# Controller.net
KiCad netlist of a schematic drawn in Altium Designer
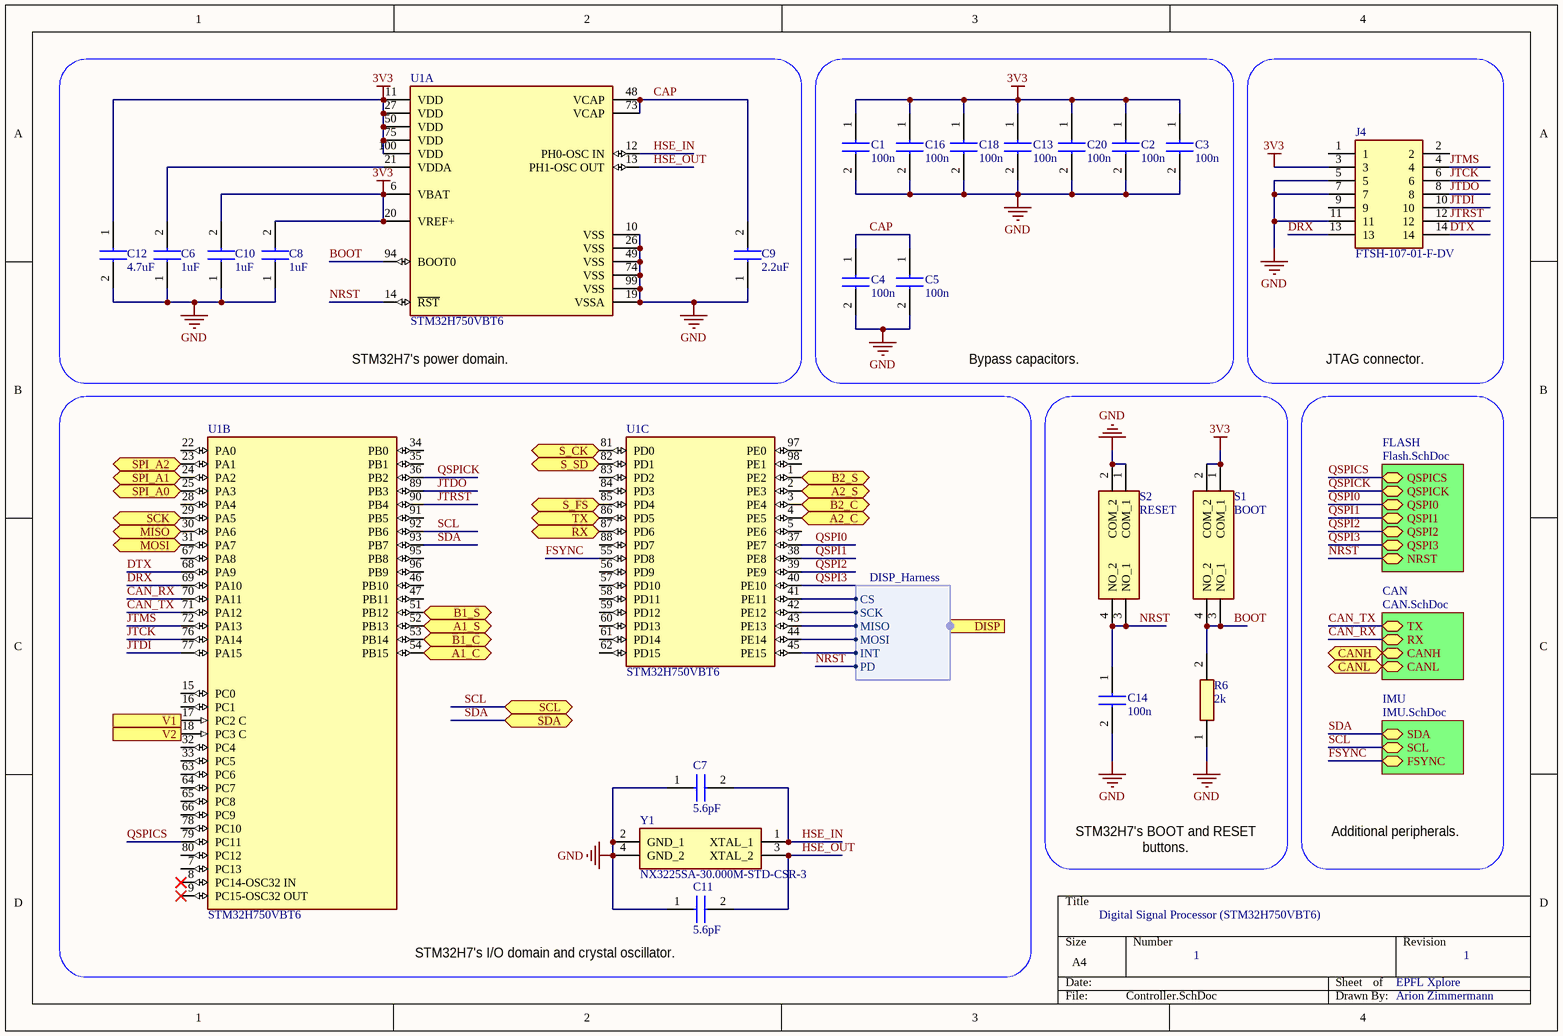
[diagram p0: Controller.SchDoc]

(export (version "E")
  (design (tool "Eeschema 10.0.6"))
  (components
    (comp (ref "C1")
      (value "100n")
      (footprint "SamacSys:CAPC1608X95N")
      (description "Capacitor")
      (fields
        (field (name "MANUFACTURER_PART_NUMBER") "C0603C104K5RACTU")
        (field (name "MOUSER PART NUMBER") "80-C0603C104K5R")
      )
      (libsource (lib "CarrierBoard") (part "C0603C104K5RACTU"))
    )
    (comp (ref "C2")
      (value "100n")
      (footprint "SamacSys:CAPC1608X95N")
      (description "Capacitor")
      (fields
        (field (name "MANUFACTURER_PART_NUMBER") "C0603C104K5RACTU")
        (field (name "MOUSER PART NUMBER") "80-C0603C104K5R")
      )
      (libsource (lib "CarrierBoard") (part "C0603C104K5RACTU"))
    )
    (comp (ref "C3")
      (value "100n")
      (footprint "SamacSys:CAPC1608X95N")
      (description "Capacitor")
      (fields
        (field (name "MANUFACTURER_PART_NUMBER") "C0603C104K5RACTU")
        (field (name "MOUSER PART NUMBER") "80-C0603C104K5R")
      )
      (libsource (lib "CarrierBoard") (part "C0603C104K5RACTU"))
    )
    (comp (ref "C4")
      (value "100n")
      (footprint "SamacSys:CAPC1608X95N")
      (description "Capacitor")
      (fields
        (field (name "MANUFACTURER_PART_NUMBER") "C0603C104K5RACTU")
        (field (name "MOUSER PART NUMBER") "80-C0603C104K5R")
      )
      (libsource (lib "CarrierBoard") (part "C0603C104K5RACTU"))
    )
    (comp (ref "C5")
      (value "100n")
      (footprint "SamacSys:CAPC1608X95N")
      (description "Capacitor")
      (fields
        (field (name "MANUFACTURER_PART_NUMBER") "C0603C104K5RACTU")
        (field (name "MOUSER PART NUMBER") "80-C0603C104K5R")
      )
      (libsource (lib "CarrierBoard") (part "C0603C104K5RACTU"))
    )
    (comp (ref "C6")
      (value "1uF")
      (footprint "SamacSys:CAPC3216X130N")
      (description "Capacitor")
      (fields
        (field (name "MANUFACTURER_PART_NUMBER") "C1206C105M5RECTU")
        (field (name "MOUSER PART NUMBER") "80-C1206C105M5RECTU")
      )
      (libsource (lib "CarrierBoard") (part "C1206C105M5RECTU"))
    )
    (comp (ref "C7")
      (value "5.6pF")
      (footprint "SamacSys:CAPC1608X87N")
      (description "Capacitor")
      (fields
        (field (name "MANUFACTURER_PART_NUMBER") "CBR06C569B5GAC")
        (field (name "MOUSER PART NUMBER") "80-CBR06C569B5GAC")
      )
      (libsource (lib "CarrierBoard") (part "CBR06C569B5GAC"))
    )
    (comp (ref "C8")
      (value "1uF")
      (footprint "SamacSys:CAPC3216X130N")
      (description "Capacitor")
      (fields
        (field (name "MANUFACTURER_PART_NUMBER") "C1206C105M5RECTU")
        (field (name "MOUSER PART NUMBER") "80-C1206C105M5RECTU")
      )
      (libsource (lib "CarrierBoard") (part "C1206C105M5RECTU"))
    )
    (comp (ref "C9")
      (value "2.2uF")
      (footprint "SamacSys:CAPC2012X140N")
      (description "Capacitor")
      (fields
        (field (name "MANUFACTURER_PART_NUMBER") "C0805C225K4REC7210")
        (field (name "MOUSER PART NUMBER") "80-C0805C225K4RECLR")
      )
      (libsource (lib "CarrierBoard") (part "C0805C225K4REC7210"))
    )
    (comp (ref "C10")
      (value "1uF")
      (footprint "SamacSys:CAPC3216X130N")
      (description "Capacitor")
      (fields
        (field (name "MANUFACTURER_PART_NUMBER") "C1206C105M5RECTU")
        (field (name "MOUSER PART NUMBER") "80-C1206C105M5RECTU")
      )
      (libsource (lib "CarrierBoard") (part "C1206C105M5RECTU"))
    )
    (comp (ref "C11")
      (value "5.6pF")
      (footprint "SamacSys:CAPC1608X87N")
      (description "Capacitor")
      (fields
        (field (name "MANUFACTURER_PART_NUMBER") "CBR06C569B5GAC")
        (field (name "MOUSER PART NUMBER") "80-CBR06C569B5GAC")
      )
      (libsource (lib "CarrierBoard") (part "CBR06C569B5GAC"))
    )
    (comp (ref "C12")
      (value "4.7uF")
      (footprint "SamacSys:CAPC2012X140N")
      (description "Capacitor")
      (fields
        (field (name "MANUFACTURER_PART_NUMBER") "C0805C475J4RACAUTO")
        (field (name "MOUSER PART NUMBER") "80-C0805C475J4RAUTO")
      )
      (libsource (lib "CarrierBoard") (part "C0805C475J4RACAUTO"))
    )
    (comp (ref "C13")
      (value "100n")
      (footprint "SamacSys:CAPC1608X95N")
      (description "Capacitor")
      (fields
        (field (name "MANUFACTURER_PART_NUMBER") "C0603C104K5RACTU")
        (field (name "MOUSER PART NUMBER") "80-C0603C104K5R")
      )
      (libsource (lib "CarrierBoard") (part "C0603C104K5RACTU"))
    )
    (comp (ref "C14")
      (value "100n")
      (footprint "SamacSys:CAPC1608X95N")
      (description "Capacitor")
      (fields
        (field (name "MANUFACTURER_PART_NUMBER") "C0603C104K5RACTU")
        (field (name "MOUSER PART NUMBER") "80-C0603C104K5R")
      )
      (libsource (lib "CarrierBoard") (part "C0603C104K5RACTU"))
    )
    (comp (ref "C16")
      (value "100n")
      (footprint "SamacSys:CAPC1608X95N")
      (description "Capacitor")
      (fields
        (field (name "MANUFACTURER_PART_NUMBER") "C0603C104K5RACTU")
        (field (name "MOUSER PART NUMBER") "80-C0603C104K5R")
      )
      (libsource (lib "CarrierBoard") (part "C0603C104K5RACTU"))
    )
    (comp (ref "C18")
      (value "100n")
      (footprint "SamacSys:CAPC1608X95N")
      (description "Capacitor")
      (fields
        (field (name "MANUFACTURER_PART_NUMBER") "C0603C104K5RACTU")
        (field (name "MOUSER PART NUMBER") "80-C0603C104K5R")
      )
      (libsource (lib "CarrierBoard") (part "C0603C104K5RACTU"))
    )
    (comp (ref "C20")
      (value "100n")
      (footprint "SamacSys:CAPC1608X95N")
      (description "Capacitor")
      (fields
        (field (name "MANUFACTURER_PART_NUMBER") "C0603C104K5RACTU")
        (field (name "MOUSER PART NUMBER") "80-C0603C104K5R")
      )
      (libsource (lib "CarrierBoard") (part "C0603C104K5RACTU"))
    )
    (comp (ref "J4")
      (value "FTSH-107-01-F-DV")
      (footprint "SamacSys:FTSH-107-XX-YYY-DV")
      (description "Connector")
      (fields (field (name "MOUSER PART NUMBER") "200-FTSH10701FDV"))
      (libsource (lib "CarrierBoard") (part "FTSH-107-01-F-DV"))
    )
    (comp (ref "R6")
      (value "2k")
      (footprint "SamacSys:RESC1608X50N")
      (description "Resistor")
      (fields
        (field (name "MANUFACTURER_PART_NUMBER") "CRCW0603787RFKEA")
        (field (name "Comment") "CRCW06032K00JNEB")
      )
      (libsource (lib "CarrierBoard") (part "CRCW0603931RFKEA"))
    )
    (comp (ref "S1")
      (value "BOOT")
      (footprint "LL3301FF065QJ")
      (description "Switch")
      (fields
        (field (name "MANUFACTURER_PART_NUMBER") "LL3301AF065QJ")
        (field (name "MOUSER PART NUMBER") "612-LL3301AF065QJ")
      )
      (libsource (lib "CarrierBoard") (part "LL3301AF065QJ"))
    )
    (comp (ref "S2")
      (value "RESET")
      (footprint "LL3301FF065QJ")
      (description "Switch")
      (fields
        (field (name "MANUFACTURER_PART_NUMBER") "LL3301AF065QJ")
        (field (name "MOUSER PART NUMBER") "612-LL3301AF065QJ")
      )
      (libsource (lib "CarrierBoard") (part "LL3301AF065QJ"))
    )
    (comp (ref "U1")
      (value "STM32H750VBT6")
      (footprint "FP-LQFP100-1L-MFG")
      (description "IC MCU 32BIT 128KB FLASH 100LQFP")
      (fields
        (field (name "OCTOPART") "https://octopart.com/stm32h750vbt6-stmicroelectronics-94048547")
        (field (name "MANUFACTURER") "STMicroelectronics")
      )
      (libsource (lib "Altium Content Vault") (part "aca449acb2b80670ba40d015d68dc7a"))
    )
    (comp (ref "Y1")
      (value "NX3225SA-30.000M-STD-CSR-3")
      (footprint "SamacSys:NX2520SA192MHzEXS00ACS05400")
      (description "Crystal or Oscillator")
      (fields
        (field (name "MANUFACTURER_PART_NUMBER") "NX2520SA-25.000M-STD-CSW-5")
        (field (name "MOUSER PART NUMBER") "344-NX2520SA25MSTSW5")
      )
      (libsource (lib "CarrierBoard") (part "NX2520SA-25.000M-STD-CSW-5"))
    )
  )
  (nets
    (net (code "2") (name "/A1_C") (class "Default")
      (node (ref "U1") (pin "54") (pinfunction "PB15_54") (pintype "bidirectional"))
    )
    (net (code "3") (name "/A1_S") (class "Default")
      (node (ref "U1") (pin "52") (pinfunction "PB13_52") (pintype "bidirectional"))
    )
    (net (code "4") (name "/A2_C") (class "Default")
      (node (ref "U1") (pin "4") (pinfunction "PE5_4") (pintype "bidirectional"))
    )
    (net (code "5") (name "/A2_S") (class "Default")
      (node (ref "U1") (pin "2") (pinfunction "PE3_2") (pintype "bidirectional"))
    )
    (net (code "6") (name "/B1_C") (class "Default")
      (node (ref "U1") (pin "53") (pinfunction "PB14_53") (pintype "bidirectional"))
    )
    (net (code "7") (name "/B1_S") (class "Default")
      (node (ref "U1") (pin "51") (pinfunction "PB12_51") (pintype "bidirectional"))
    )
    (net (code "8") (name "/B2_C") (class "Default")
      (node (ref "U1") (pin "3") (pinfunction "PE4_3") (pintype "bidirectional"))
    )
    (net (code "9") (name "/B2_S") (class "Default")
      (node (ref "U1") (pin "1") (pinfunction "PE2_1") (pintype "bidirectional"))
    )
    (net (code "10") (name "/BOOT") (class "Default")
      (node (ref "R6") (pin "2") (pinfunction "2_2") (pintype "passive"))
      (node (ref "S1") (pin "3") (pinfunction "NO_1_3") (pintype "passive"))
      (node (ref "S1") (pin "4") (pinfunction "NO_2_4") (pintype "passive"))
      (node (ref "U1") (pin "94") (pinfunction "BOOT0_94") (pintype "input"))
    )
    (net (code "13") (name "/CAN_RX") (class "Default")
      (node (ref "U1") (pin "70") (pinfunction "PA11_70") (pintype "bidirectional"))
    )
    (net (code "14") (name "/CAN_TX") (class "Default")
      (node (ref "U1") (pin "71") (pinfunction "PA12_71") (pintype "bidirectional"))
    )
    (net (code "15") (name "/CAP") (class "Default")
      (node (ref "C4") (pin "1") (pinfunction "1_1") (pintype "passive"))
      (node (ref "C5") (pin "1") (pinfunction "1_1") (pintype "passive"))
      (node (ref "C9") (pin "2") (pinfunction "2_2") (pintype "passive"))
      (node (ref "U1") (pin "48") (pinfunction "VCAP_48") (pintype "power_in"))
      (node (ref "U1") (pin "73") (pinfunction "VCAP_73") (pintype "power_in"))
    )
    (net (code "16") (name "/CS") (class "Default")
      (node (ref "U1") (pin "41") (pinfunction "PE11_41") (pintype "bidirectional"))
    )
    (net (code "17") (name "/DRX") (class "Default")
      (node (ref "J4") (pin "13") (pinfunction "13_13") (pintype "passive"))
      (node (ref "U1") (pin "69") (pinfunction "PA10_69") (pintype "bidirectional"))
    )
    (net (code "18") (name "/DTX") (class "Default")
      (node (ref "J4") (pin "14") (pinfunction "14_14") (pintype "passive"))
      (node (ref "U1") (pin "68") (pinfunction "PA9_68") (pintype "bidirectional"))
    )
    (net (code "19") (name "/FSYNC") (class "Default")
      (node (ref "U1") (pin "55") (pinfunction "PD8_55") (pintype "bidirectional"))
    )
    (net (code "20") (name "/HSE_IN") (class "Default")
      (node (ref "C7") (pin "2") (pinfunction "2_2") (pintype "passive"))
      (node (ref "U1") (pin "12") (pinfunction "PH0-OSC_IN_12") (pintype "bidirectional"))
      (node (ref "Y1") (pin "1") (pinfunction "XTAL_1_1") (pintype "passive"))
    )
    (net (code "21") (name "/HSE_OUT") (class "Default")
      (node (ref "C11") (pin "2") (pinfunction "2_2") (pintype "passive"))
      (node (ref "U1") (pin "13") (pinfunction "PH1-OSC_OUT_13") (pintype "bidirectional"))
      (node (ref "Y1") (pin "3") (pinfunction "XTAL_2_3") (pintype "passive"))
    )
    (net (code "22") (name "/INT") (class "Default")
      (node (ref "U1") (pin "45") (pinfunction "PE15_45") (pintype "bidirectional"))
    )
    (net (code "23") (name "/JTCK") (class "Default")
      (node (ref "J4") (pin "6") (pinfunction "6_6") (pintype "passive"))
      (node (ref "U1") (pin "76") (pinfunction "PA14_76") (pintype "bidirectional"))
    )
    (net (code "24") (name "/JTDI") (class "Default")
      (node (ref "J4") (pin "10") (pinfunction "10_10") (pintype "passive"))
      (node (ref "U1") (pin "77") (pinfunction "PA15_77") (pintype "bidirectional"))
    )
    (net (code "25") (name "/JTDO") (class "Default")
      (node (ref "J4") (pin "8") (pinfunction "8_8") (pintype "passive"))
      (node (ref "U1") (pin "89") (pinfunction "PB3_89") (pintype "bidirectional"))
    )
    (net (code "26") (name "/JTMS") (class "Default")
      (node (ref "J4") (pin "4") (pinfunction "4_4") (pintype "passive"))
      (node (ref "U1") (pin "72") (pinfunction "PA13_72") (pintype "bidirectional"))
    )
    (net (code "27") (name "/JTRST") (class "Default")
      (node (ref "J4") (pin "12") (pinfunction "12_12") (pintype "passive"))
      (node (ref "U1") (pin "90") (pinfunction "PB4_90") (pintype "bidirectional"))
    )
    (net (code "28") (name "/MISO") (class "Default")
      (node (ref "U1") (pin "30") (pinfunction "PA6_30") (pintype "bidirectional"))
    )
    (net (code "29") (name "/MOSI") (class "Default")
      (node (ref "U1") (pin "31") (pinfunction "PA7_31") (pintype "bidirectional"))
    )
    (net (code "30") (name "/NRST") (class "Default")
      (node (ref "C14") (pin "1") (pinfunction "1_1") (pintype "passive"))
      (node (ref "S2") (pin "3") (pinfunction "NO_1_3") (pintype "passive"))
      (node (ref "S2") (pin "4") (pinfunction "NO_2_4") (pintype "passive"))
      (node (ref "U1") (pin "14") (pinfunction "~{RST}_14") (pintype "bidirectional"))
    )
    (net (code "31") (name "/QSPI0") (class "Default")
      (node (ref "U1") (pin "37") (pinfunction "PE7_37") (pintype "bidirectional"))
    )
    (net (code "32") (name "/QSPI1") (class "Default")
      (node (ref "U1") (pin "38") (pinfunction "PE8_38") (pintype "bidirectional"))
    )
    (net (code "33") (name "/QSPI2") (class "Default")
      (node (ref "U1") (pin "39") (pinfunction "PE9_39") (pintype "bidirectional"))
    )
    (net (code "34") (name "/QSPI3") (class "Default")
      (node (ref "U1") (pin "40") (pinfunction "PE10_40") (pintype "bidirectional"))
    )
    (net (code "35") (name "/QSPICK") (class "Default")
      (node (ref "U1") (pin "36") (pinfunction "PB2_36") (pintype "bidirectional"))
    )
    (net (code "36") (name "/QSPICS") (class "Default")
      (node (ref "U1") (pin "79") (pinfunction "PC11_79") (pintype "bidirectional"))
    )
    (net (code "37") (name "/RX") (class "Default")
      (node (ref "U1") (pin "87") (pinfunction "PD6_87") (pintype "bidirectional"))
    )
    (net (code "38") (name "/SCK") (class "Default")
      (node (ref "U1") (pin "29") (pinfunction "PA5_29") (pintype "bidirectional"))
    )
    (net (code "39") (name "/SCL") (class "Default")
      (node (ref "U1") (pin "92") (pinfunction "PB6_92") (pintype "bidirectional"))
    )
    (net (code "40") (name "/SDA") (class "Default")
      (node (ref "U1") (pin "93") (pinfunction "PB7_93") (pintype "bidirectional"))
    )
    (net (code "41") (name "/SPI_A0") (class "Default")
      (node (ref "U1") (pin "25") (pinfunction "PA3_25") (pintype "bidirectional"))
    )
    (net (code "42") (name "/SPI_A1") (class "Default")
      (node (ref "U1") (pin "24") (pinfunction "PA2_24") (pintype "bidirectional"))
    )
    (net (code "43") (name "/SPI_A2") (class "Default")
      (node (ref "U1") (pin "23") (pinfunction "PA1_23") (pintype "bidirectional"))
    )
    (net (code "44") (name "/S_CK") (class "Default")
      (node (ref "U1") (pin "81") (pinfunction "PD0_81") (pintype "bidirectional"))
    )
    (net (code "45") (name "/S_FS") (class "Default")
      (node (ref "U1") (pin "85") (pinfunction "PD4_85") (pintype "bidirectional"))
    )
    (net (code "46") (name "/S_SD") (class "Default")
      (node (ref "U1") (pin "82") (pinfunction "PD1_82") (pintype "bidirectional"))
    )
    (net (code "47") (name "/TX") (class "Default")
      (node (ref "U1") (pin "86") (pinfunction "PD5_86") (pintype "bidirectional"))
    )
    (net (code "48") (name "/V1") (class "Default")
      (node (ref "U1") (pin "17") (pinfunction "PC2_C_17") (pintype "input"))
    )
    (net (code "49") (name "/V2") (class "Default")
      (node (ref "U1") (pin "18") (pinfunction "PC3_C_18") (pintype "input"))
    )
    (net (code "51") (name "3V3") (class "Default")
      (node (ref "C1") (pin "1") (pinfunction "1_1") (pintype "passive"))
      (node (ref "C10") (pin "2") (pinfunction "2_2") (pintype "passive"))
      (node (ref "C12") (pin "1") (pinfunction "1_1") (pintype "passive"))
      (node (ref "C13") (pin "1") (pinfunction "1_1") (pintype "passive"))
      (node (ref "C16") (pin "1") (pinfunction "1_1") (pintype "passive"))
      (node (ref "C18") (pin "1") (pinfunction "1_1") (pintype "passive"))
      (node (ref "C2") (pin "1") (pinfunction "1_1") (pintype "passive"))
      (node (ref "C20") (pin "1") (pinfunction "1_1") (pintype "passive"))
      (node (ref "C3") (pin "1") (pinfunction "1_1") (pintype "passive"))
      (node (ref "C8") (pin "2") (pinfunction "2_2") (pintype "passive"))
      (node (ref "J4") (pin "3") (pinfunction "3_3") (pintype "passive"))
      (node (ref "S1") (pin "1") (pinfunction "COM_1_1") (pintype "passive"))
      (node (ref "S1") (pin "2") (pinfunction "COM_2_2") (pintype "passive"))
      (node (ref "U1") (pin "100") (pinfunction "VDD_100") (pintype "power_in"))
      (node (ref "U1") (pin "11") (pinfunction "VDD_11") (pintype "power_in"))
      (node (ref "U1") (pin "20") (pinfunction "VREF+_20") (pintype "power_in"))
      (node (ref "U1") (pin "27") (pinfunction "VDD_27") (pintype "power_in"))
      (node (ref "U1") (pin "50") (pinfunction "VDD_50") (pintype "power_in"))
      (node (ref "U1") (pin "6") (pinfunction "VBAT_6") (pintype "power_in"))
      (node (ref "U1") (pin "75") (pinfunction "VDD_75") (pintype "power_in"))
    )
    (net (code "52") (name "GND") (class "Default")
      (node (ref "C1") (pin "2") (pinfunction "2_2") (pintype "passive"))
      (node (ref "C10") (pin "1") (pinfunction "1_1") (pintype "passive"))
      (node (ref "C11") (pin "1") (pinfunction "1_1") (pintype "passive"))
      (node (ref "C12") (pin "2") (pinfunction "2_2") (pintype "passive"))
      (node (ref "C13") (pin "2") (pinfunction "2_2") (pintype "passive"))
      (node (ref "C14") (pin "2") (pinfunction "2_2") (pintype "passive"))
      (node (ref "C16") (pin "2") (pinfunction "2_2") (pintype "passive"))
      (node (ref "C18") (pin "2") (pinfunction "2_2") (pintype "passive"))
      (node (ref "C2") (pin "2") (pinfunction "2_2") (pintype "passive"))
      (node (ref "C20") (pin "2") (pinfunction "2_2") (pintype "passive"))
      (node (ref "C3") (pin "2") (pinfunction "2_2") (pintype "passive"))
      (node (ref "C4") (pin "2") (pinfunction "2_2") (pintype "passive"))
      (node (ref "C5") (pin "2") (pinfunction "2_2") (pintype "passive"))
      (node (ref "C6") (pin "1") (pinfunction "1_1") (pintype "passive"))
      (node (ref "C7") (pin "1") (pinfunction "1_1") (pintype "passive"))
      (node (ref "C8") (pin "1") (pinfunction "1_1") (pintype "passive"))
      (node (ref "C9") (pin "1") (pinfunction "1_1") (pintype "passive"))
      (node (ref "J4") (pin "11") (pinfunction "11_11") (pintype "passive"))
      (node (ref "J4") (pin "5") (pinfunction "5_5") (pintype "passive"))
      (node (ref "J4") (pin "7") (pinfunction "7_7") (pintype "passive"))
      (node (ref "R6") (pin "1") (pinfunction "1_1") (pintype "passive"))
      (node (ref "S2") (pin "1") (pinfunction "COM_1_1") (pintype "passive"))
      (node (ref "S2") (pin "2") (pinfunction "COM_2_2") (pintype "passive"))
      (node (ref "U1") (pin "10") (pinfunction "VSS_10") (pintype "power_in"))
      (node (ref "U1") (pin "19") (pinfunction "VSSA_19") (pintype "power_in"))
      (node (ref "U1") (pin "26") (pinfunction "VSS_26") (pintype "power_in"))
      (node (ref "U1") (pin "49") (pinfunction "VSS_49") (pintype "power_in"))
      (node (ref "U1") (pin "74") (pinfunction "VSS_74") (pintype "power_in"))
      (node (ref "U1") (pin "99") (pinfunction "VSS_99") (pintype "power_in"))
      (node (ref "Y1") (pin "2") (pinfunction "GND_1_2") (pintype "passive"))
      (node (ref "Y1") (pin "4") (pinfunction "GND_2_4") (pintype "passive"))
    )
    (net (code "53") (name "Net-(U1A-VDDA)") (class "Default")
      (node (ref "C6") (pin "2") (pinfunction "2_2") (pintype "passive"))
      (node (ref "U1") (pin "21") (pinfunction "VDDA_21") (pintype "power_in"))
    )
    (net (code "54") (name "unconnected-(J4-Pad1)") (class "Default")
      (node (ref "J4") (pin "1") (pinfunction "1_1") (pintype "passive"))
    )
    (net (code "55") (name "unconnected-(J4-Pad2)") (class "Default")
      (node (ref "J4") (pin "2") (pinfunction "2_2") (pintype "passive"))
    )
    (net (code "56") (name "unconnected-(J4-Pad9)") (class "Default")
      (node (ref "J4") (pin "9") (pinfunction "9_9") (pintype "passive"))
    )
    (net (code "57") (name "unconnected-(U1B-PA0-Pad22)") (class "Default")
      (node (ref "U1") (pin "22") (pinfunction "PA0_22") (pintype "bidirectional"))
    )
    (net (code "58") (name "unconnected-(U1B-PA4-Pad28)") (class "Default")
      (node (ref "U1") (pin "28") (pinfunction "PA4_28") (pintype "bidirectional"))
    )
    (net (code "59") (name "unconnected-(U1B-PA8-Pad67)") (class "Default")
      (node (ref "U1") (pin "67") (pinfunction "PA8_67") (pintype "bidirectional"))
    )
    (net (code "60") (name "unconnected-(U1B-PB0-Pad34)") (class "Default")
      (node (ref "U1") (pin "34") (pinfunction "PB0_34") (pintype "bidirectional"))
    )
    (net (code "61") (name "unconnected-(U1B-PB1-Pad35)") (class "Default")
      (node (ref "U1") (pin "35") (pinfunction "PB1_35") (pintype "bidirectional"))
    )
    (net (code "62") (name "unconnected-(U1B-PB5-Pad91)") (class "Default")
      (node (ref "U1") (pin "91") (pinfunction "PB5_91") (pintype "bidirectional"))
    )
    (net (code "63") (name "unconnected-(U1B-PB8-Pad95)") (class "Default")
      (node (ref "U1") (pin "95") (pinfunction "PB8_95") (pintype "bidirectional"))
    )
    (net (code "64") (name "unconnected-(U1B-PB9-Pad96)") (class "Default")
      (node (ref "U1") (pin "96") (pinfunction "PB9_96") (pintype "bidirectional"))
    )
    (net (code "65") (name "unconnected-(U1B-PB10-Pad46)") (class "Default")
      (node (ref "U1") (pin "46") (pinfunction "PB10_46") (pintype "bidirectional"))
    )
    (net (code "66") (name "unconnected-(U1B-PB11-Pad47)") (class "Default")
      (node (ref "U1") (pin "47") (pinfunction "PB11_47") (pintype "bidirectional"))
    )
    (net (code "67") (name "unconnected-(U1B-PC0-Pad15)") (class "Default")
      (node (ref "U1") (pin "15") (pinfunction "PC0_15") (pintype "bidirectional"))
    )
    (net (code "68") (name "unconnected-(U1B-PC1-Pad16)") (class "Default")
      (node (ref "U1") (pin "16") (pinfunction "PC1_16") (pintype "bidirectional"))
    )
    (net (code "69") (name "unconnected-(U1B-PC4-Pad32)") (class "Default")
      (node (ref "U1") (pin "32") (pinfunction "PC4_32") (pintype "bidirectional"))
    )
    (net (code "70") (name "unconnected-(U1B-PC5-Pad33)") (class "Default")
      (node (ref "U1") (pin "33") (pinfunction "PC5_33") (pintype "bidirectional"))
    )
    (net (code "71") (name "unconnected-(U1B-PC6-Pad63)") (class "Default")
      (node (ref "U1") (pin "63") (pinfunction "PC6_63") (pintype "bidirectional"))
    )
    (net (code "72") (name "unconnected-(U1B-PC7-Pad64)") (class "Default")
      (node (ref "U1") (pin "64") (pinfunction "PC7_64") (pintype "bidirectional"))
    )
    (net (code "73") (name "unconnected-(U1B-PC8-Pad65)") (class "Default")
      (node (ref "U1") (pin "65") (pinfunction "PC8_65") (pintype "bidirectional"))
    )
    (net (code "74") (name "unconnected-(U1B-PC9-Pad66)") (class "Default")
      (node (ref "U1") (pin "66") (pinfunction "PC9_66") (pintype "bidirectional"))
    )
    (net (code "75") (name "unconnected-(U1B-PC10-Pad78)") (class "Default")
      (node (ref "U1") (pin "78") (pinfunction "PC10_78") (pintype "bidirectional"))
    )
    (net (code "76") (name "unconnected-(U1B-PC12-Pad80)") (class "Default")
      (node (ref "U1") (pin "80") (pinfunction "PC12_80") (pintype "bidirectional"))
    )
    (net (code "77") (name "unconnected-(U1B-PC13-Pad7)") (class "Default")
      (node (ref "U1") (pin "7") (pinfunction "PC13_7") (pintype "bidirectional"))
    )
    (net (code "78") (name "unconnected-(U1B-PC14-OSC32_IN-Pad8)") (class "Default")
      (node (ref "U1") (pin "8") (pinfunction "PC14-OSC32_IN_8") (pintype "bidirectional+no_connect"))
    )
    (net (code "79") (name "unconnected-(U1B-PC15-OSC32_OUT-Pad9)") (class "Default")
      (node (ref "U1") (pin "9") (pinfunction "PC15-OSC32_OUT_9") (pintype "bidirectional+no_connect"))
    )
    (net (code "80") (name "unconnected-(U1C-PD2-Pad83)") (class "Default")
      (node (ref "U1") (pin "83") (pinfunction "PD2_83") (pintype "bidirectional"))
    )
    (net (code "81") (name "unconnected-(U1C-PD3-Pad84)") (class "Default")
      (node (ref "U1") (pin "84") (pinfunction "PD3_84") (pintype "bidirectional"))
    )
    (net (code "82") (name "unconnected-(U1C-PD7-Pad88)") (class "Default")
      (node (ref "U1") (pin "88") (pinfunction "PD7_88") (pintype "bidirectional"))
    )
    (net (code "83") (name "unconnected-(U1C-PD9-Pad56)") (class "Default")
      (node (ref "U1") (pin "56") (pinfunction "PD9_56") (pintype "bidirectional"))
    )
    (net (code "84") (name "unconnected-(U1C-PD10-Pad57)") (class "Default")
      (node (ref "U1") (pin "57") (pinfunction "PD10_57") (pintype "bidirectional"))
    )
    (net (code "85") (name "unconnected-(U1C-PD11-Pad58)") (class "Default")
      (node (ref "U1") (pin "58") (pinfunction "PD11_58") (pintype "bidirectional"))
    )
    (net (code "86") (name "unconnected-(U1C-PD12-Pad59)") (class "Default")
      (node (ref "U1") (pin "59") (pinfunction "PD12_59") (pintype "bidirectional"))
    )
    (net (code "87") (name "unconnected-(U1C-PD13-Pad60)") (class "Default")
      (node (ref "U1") (pin "60") (pinfunction "PD13_60") (pintype "bidirectional"))
    )
    (net (code "88") (name "unconnected-(U1C-PD14-Pad61)") (class "Default")
      (node (ref "U1") (pin "61") (pinfunction "PD14_61") (pintype "bidirectional"))
    )
    (net (code "89") (name "unconnected-(U1C-PD15-Pad62)") (class "Default")
      (node (ref "U1") (pin "62") (pinfunction "PD15_62") (pintype "bidirectional"))
    )
    (net (code "90") (name "unconnected-(U1C-PE0-Pad97)") (class "Default")
      (node (ref "U1") (pin "97") (pinfunction "PE0_97") (pintype "bidirectional"))
    )
    (net (code "91") (name "unconnected-(U1C-PE1-Pad98)") (class "Default")
      (node (ref "U1") (pin "98") (pinfunction "PE1_98") (pintype "bidirectional"))
    )
    (net (code "92") (name "unconnected-(U1C-PE6-Pad5)") (class "Default")
      (node (ref "U1") (pin "5") (pinfunction "PE6_5") (pintype "bidirectional"))
    )
    (net (code "93") (name "unconnected-(U1C-PE12-Pad42)") (class "Default")
      (node (ref "U1") (pin "42") (pinfunction "PE12_42") (pintype "bidirectional"))
    )
    (net (code "94") (name "unconnected-(U1C-PE13-Pad43)") (class "Default")
      (node (ref "U1") (pin "43") (pinfunction "PE13_43") (pintype "bidirectional"))
    )
    (net (code "95") (name "unconnected-(U1C-PE14-Pad44)") (class "Default")
      (node (ref "U1") (pin "44") (pinfunction "PE14_44") (pintype "bidirectional"))
    )
  )
)
